# QSFP.net
KiCad netlist of a schematic drawn in Altium Designer
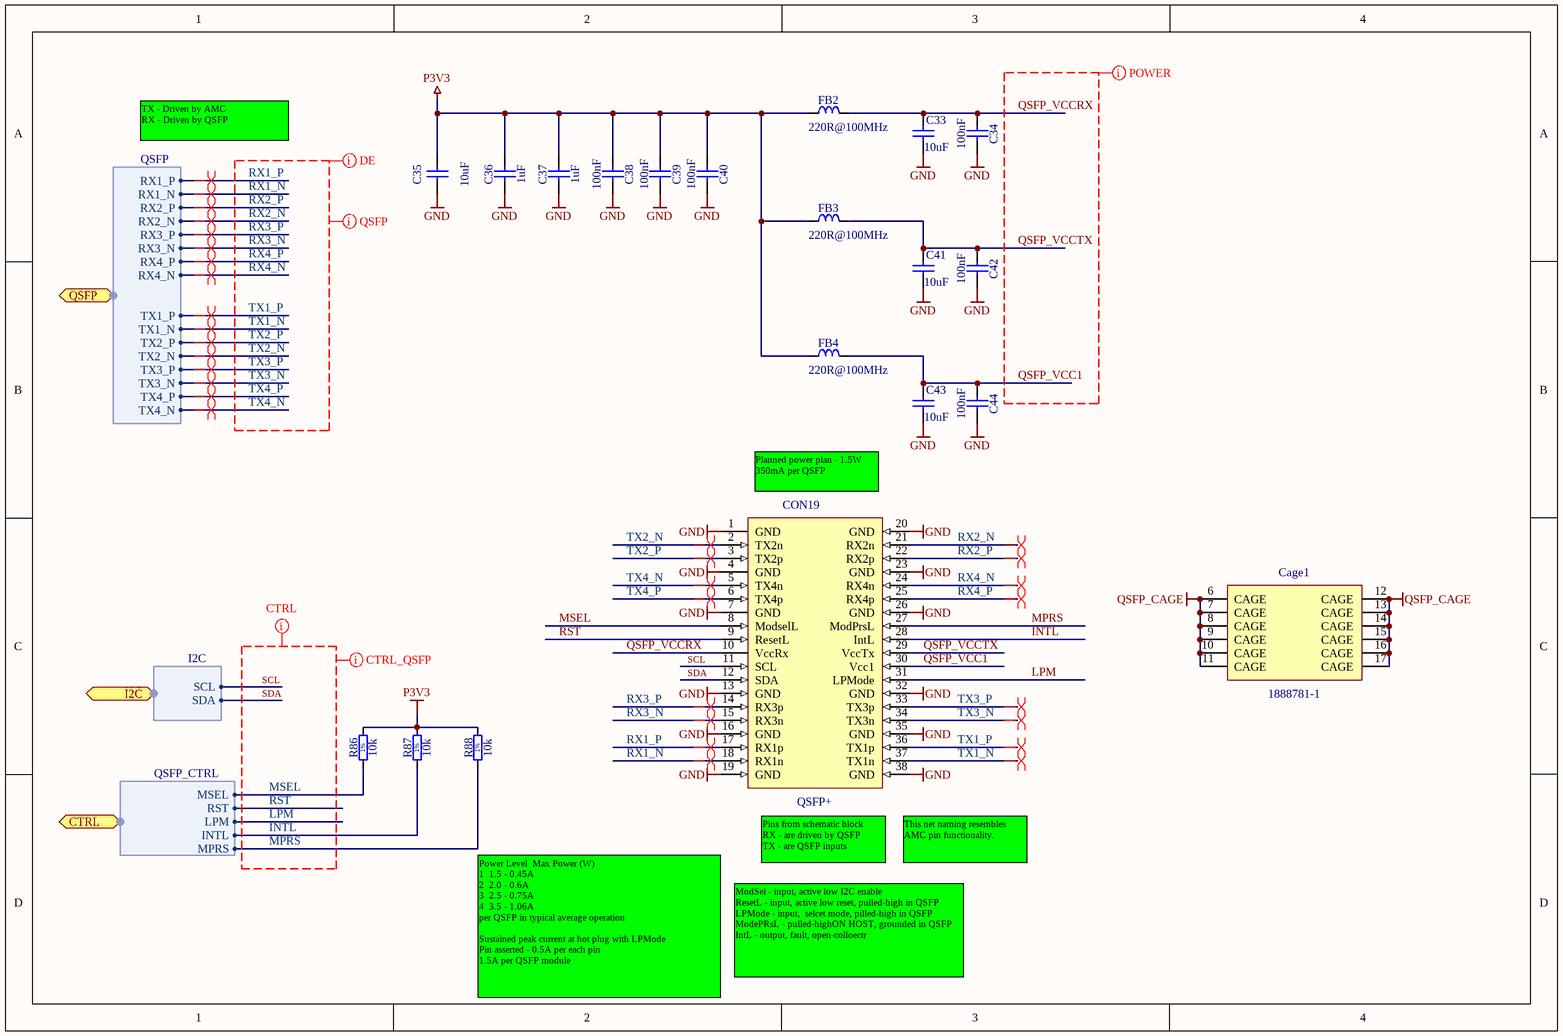
[diagram p0: QSFP.SchDoc]

(export (version "E")
  (design (tool "Eeschema 10.0.6"))
  (components
    (comp (ref "C33")
      (value "10uF")
      (footprint "CAPC2012X135N")
      (description "Non-polarised capacitor")
      (fields
        (field (name "PART NUMBER") "CC0805_10UF_10V_10%_X7R")
        (field (name "VOLTAGE") "10V")
        (field (name "AUTHOR") "CERN DEM JLC")
      )
      (libsource (lib "Capacitors") (part "Capacitor - non polarized"))
    )
    (comp (ref "C34")
      (value "100nF")
      (footprint "CAPC0603X33N")
      (description "Non-polarised capacitor")
      (fields
        (field (name "PART NUMBER") "CC0201_100NF_6.3V_10%_X5R")
        (field (name "VOLTAGE") "6.3V")
        (field (name "AUTHOR") "CERN DEM JLC")
      )
      (libsource (lib "Capacitors") (part "Capacitor - non polarized"))
    )
    (comp (ref "C35")
      (value "10uF")
      (footprint "CAPC2012X135N")
      (description "Non-polarised capacitor")
      (fields
        (field (name "PART NUMBER") "CC0805_10UF_10V_10%_X7R")
        (field (name "VOLTAGE") "10V")
        (field (name "AUTHOR") "CERN DEM JLC")
      )
      (libsource (lib "Capacitors") (part "Capacitor - non polarized"))
    )
    (comp (ref "C36")
      (value "1uF")
      (footprint "CAPC1608X87N")
      (description "Non-polarised capacitor")
      (fields
        (field (name "PART NUMBER") "CC0603_1UF_25V_10%_X7R")
        (field (name "VOLTAGE") "25V")
        (field (name "AUTHOR") "CERN DEM JLC")
      )
      (libsource (lib "Capacitors") (part "Capacitor - non polarized"))
    )
    (comp (ref "C37")
      (value "1uF")
      (footprint "CAPC1608X87N")
      (description "Non-polarised capacitor")
      (fields
        (field (name "PART NUMBER") "CC0603_1UF_25V_10%_X7R")
        (field (name "VOLTAGE") "25V")
        (field (name "AUTHOR") "CERN DEM JLC")
      )
      (libsource (lib "Capacitors") (part "Capacitor - non polarized"))
    )
    (comp (ref "C38")
      (value "100nF")
      (footprint "CAPC0603X33N")
      (description "Non-polarised capacitor")
      (fields
        (field (name "PART NUMBER") "CC0201_100NF_6.3V_10%_X5R")
        (field (name "VOLTAGE") "6.3V")
        (field (name "AUTHOR") "CERN DEM JLC")
      )
      (libsource (lib "Capacitors") (part "Capacitor - non polarized"))
    )
    (comp (ref "C39")
      (value "100nF")
      (footprint "CAPC0603X33N")
      (description "Non-polarised capacitor")
      (fields
        (field (name "PART NUMBER") "CC0201_100NF_6.3V_10%_X5R")
        (field (name "VOLTAGE") "6.3V")
        (field (name "AUTHOR") "CERN DEM JLC")
      )
      (libsource (lib "Capacitors") (part "Capacitor - non polarized"))
    )
    (comp (ref "C40")
      (value "100nF")
      (footprint "CAPC0603X33N")
      (description "Non-polarised capacitor")
      (fields
        (field (name "PART NUMBER") "CC0201_100NF_6.3V_10%_X5R")
        (field (name "VOLTAGE") "6.3V")
        (field (name "AUTHOR") "CERN DEM JLC")
      )
      (libsource (lib "Capacitors") (part "Capacitor - non polarized"))
    )
    (comp (ref "C41")
      (value "10uF")
      (footprint "CAPC2012X135N")
      (description "Non-polarised capacitor")
      (fields
        (field (name "PART NUMBER") "CC0805_10UF_10V_10%_X7R")
        (field (name "VOLTAGE") "10V")
        (field (name "AUTHOR") "CERN DEM JLC")
      )
      (libsource (lib "Capacitors") (part "Capacitor - non polarized"))
    )
    (comp (ref "C42")
      (value "100nF")
      (footprint "CAPC0603X33N")
      (description "Non-polarised capacitor")
      (fields
        (field (name "PART NUMBER") "CC0201_100NF_6.3V_10%_X5R")
        (field (name "VOLTAGE") "6.3V")
        (field (name "AUTHOR") "CERN DEM JLC")
      )
      (libsource (lib "Capacitors") (part "Capacitor - non polarized"))
    )
    (comp (ref "C43")
      (value "10uF")
      (footprint "CAPC2012X135N")
      (description "Non-polarised capacitor")
      (fields
        (field (name "PART NUMBER") "CC0805_10UF_10V_10%_X7R")
        (field (name "VOLTAGE") "10V")
        (field (name "AUTHOR") "CERN DEM JLC")
      )
      (libsource (lib "Capacitors") (part "Capacitor - non polarized"))
    )
    (comp (ref "C44")
      (value "100nF")
      (footprint "CAPC0603X33N")
      (description "Non-polarised capacitor")
      (fields
        (field (name "PART NUMBER") "CC0201_100NF_6.3V_10%_X5R")
        (field (name "VOLTAGE") "6.3V")
        (field (name "AUTHOR") "CERN DEM JLC")
      )
      (libsource (lib "Capacitors") (part "Capacitor - non polarized"))
    )
    (comp (ref "Cage1")
      (value "1888781-1")
      (footprint "TYCO_1888617-1")
      (description "QSFP+ 1x3 Cage (23Pins)")
      (fields
        (field (name "PART NUMBER") "TYCO_2007456-1")
        (field (name "MANUFACTURER") "TYCO ELECTRONICS")
        (field (name "AUTHOR") "CERN DEM JLC")
      )
      (libsource (lib "LIBRARY_SCH") (part "CON_QSFP+_cage"))
    )
    (comp (ref "CON19")
      (value "QSFP+")
      (footprint "TYCO_1761987-9")
      (description "38Position QSFP Connector  (Quad Small Form-factor Pluggable)")
      (fields
        (field (name "PART NUMBER") "TYCO_1761987-9")
        (field (name "MANUFACTURER") "TYCO ELECTRONICS")
        (field (name "AUTHOR") "CERN DEM JLC")
      )
      (libsource (lib "Connectors") (part "QSFP+x1"))
    )
    (comp (ref "FB2")
      (value "220R@100MHz")
      (footprint "INDC2012X105N")
      (description "Inductor")
      (fields
        (field (name "PART NUMBER") "IND0805_MURATA_BLM21PG221SN1D")
        (field (name "POWER") "2A")
        (field (name "AUTHOR") "CERN DEM JLC")
      )
      (libsource (lib "Inductors & Transformers") (part "Inductor"))
    )
    (comp (ref "FB3")
      (value "220R@100MHz")
      (footprint "INDC2012X105N")
      (description "Inductor")
      (fields
        (field (name "PART NUMBER") "IND0805_MURATA_BLM21PG221SN1D")
        (field (name "POWER") "2A")
        (field (name "AUTHOR") "CERN DEM JLC")
      )
      (libsource (lib "Inductors & Transformers") (part "Inductor"))
    )
    (comp (ref "FB4")
      (value "220R@100MHz")
      (footprint "INDC2012X105N")
      (description "Inductor")
      (fields
        (field (name "PART NUMBER") "IND0805_MURATA_BLM21PG221SN1D")
        (field (name "POWER") "2A")
        (field (name "AUTHOR") "CERN DEM JLC")
      )
      (libsource (lib "Inductors & Transformers") (part "Inductor"))
    )
    (comp (ref "R86")
      (value "10k")
      (footprint "RESC1005X40N")
      (description "Resistor - 1%")
      (fields
        (field (name "PART NUMBER") "R0402_10K_1%_0.0625W_100PPM")
        (field (name "POWER") "0.0625W")
        (field (name "AUTHOR") "CERN DEM JLC")
      )
      (libsource (lib "Resistors") (part "Resistor - 1%"))
    )
    (comp (ref "R87")
      (value "10k")
      (footprint "RESC1005X40N")
      (description "Resistor - 1%")
      (fields
        (field (name "PART NUMBER") "R0402_10K_1%_0.0625W_100PPM")
        (field (name "POWER") "0.0625W")
        (field (name "AUTHOR") "CERN DEM JLC")
      )
      (libsource (lib "Resistors") (part "Resistor - 1%"))
    )
    (comp (ref "R88")
      (value "10k")
      (footprint "RESC1005X40N")
      (description "Resistor - 1%")
      (fields
        (field (name "PART NUMBER") "R0402_10K_1%_0.0625W_100PPM")
        (field (name "POWER") "0.0625W")
        (field (name "AUTHOR") "CERN DEM JLC")
      )
      (libsource (lib "Resistors") (part "Resistor - 1%"))
    )
  )
  (nets
    (net (code "4") (name "/INTL") (class "Default")
      (node (ref "CON19") (pin "28") (pinfunction "IntL_28") (pintype "input"))
      (node (ref "R87") (pin "1") (pinfunction "1_1") (pintype "passive"))
    )
    (net (code "5") (name "/LPM") (class "Default")
      (node (ref "CON19") (pin "31") (pinfunction "LPMode_31") (pintype "input"))
    )
    (net (code "6") (name "/MPRS") (class "Default")
      (node (ref "CON19") (pin "27") (pinfunction "ModPrsL_27") (pintype "input"))
      (node (ref "R88") (pin "1") (pinfunction "1_1") (pintype "passive"))
    )
    (net (code "7") (name "/MSEL") (class "Default")
      (node (ref "CON19") (pin "8") (pinfunction "ModselL_8") (pintype "input"))
      (node (ref "R86") (pin "1") (pinfunction "1_1") (pintype "passive"))
    )
    (net (code "8") (name "/QSFP_VCC1") (class "Default")
      (node (ref "C43") (pin "1") (pinfunction "1_1") (pintype "passive"))
      (node (ref "C44") (pin "1") (pinfunction "1_1") (pintype "passive"))
      (node (ref "CON19") (pin "30") (pinfunction "Vcc1_30") (pintype "input"))
      (node (ref "FB4") (pin "2") (pinfunction "2_2") (pintype "passive"))
    )
    (net (code "9") (name "/QSFP_VCCRX") (class "Default")
      (node (ref "C33") (pin "1") (pinfunction "1_1") (pintype "passive"))
      (node (ref "C34") (pin "1") (pinfunction "1_1") (pintype "passive"))
      (node (ref "CON19") (pin "10") (pinfunction "VccRx_10") (pintype "power_in"))
      (node (ref "FB2") (pin "2") (pinfunction "2_2") (pintype "passive"))
    )
    (net (code "10") (name "/QSFP_VCCTX") (class "Default")
      (node (ref "C41") (pin "1") (pinfunction "1_1") (pintype "passive"))
      (node (ref "C42") (pin "1") (pinfunction "1_1") (pintype "passive"))
      (node (ref "CON19") (pin "29") (pinfunction "VccTx_29") (pintype "input"))
      (node (ref "FB3") (pin "2") (pinfunction "2_2") (pintype "passive"))
    )
    (net (code "11") (name "/RST") (class "Default")
      (node (ref "CON19") (pin "9") (pinfunction "ResetL_9") (pintype "input"))
    )
    (net (code "12") (name "/RX1_N") (class "Default")
      (node (ref "CON19") (pin "18") (pinfunction "RX1n_18") (pintype "input"))
    )
    (net (code "13") (name "/RX1_P") (class "Default")
      (node (ref "CON19") (pin "17") (pinfunction "RX1p_17") (pintype "input"))
    )
    (net (code "14") (name "/RX2_N") (class "Default")
      (node (ref "CON19") (pin "21") (pinfunction "RX2n_21") (pintype "input"))
    )
    (net (code "15") (name "/RX2_P") (class "Default")
      (node (ref "CON19") (pin "22") (pinfunction "RX2p_22") (pintype "input"))
    )
    (net (code "16") (name "/RX3_N") (class "Default")
      (node (ref "CON19") (pin "15") (pinfunction "RX3n_15") (pintype "input"))
    )
    (net (code "17") (name "/RX3_P") (class "Default")
      (node (ref "CON19") (pin "14") (pinfunction "RX3p_14") (pintype "input"))
    )
    (net (code "18") (name "/RX4_N") (class "Default")
      (node (ref "CON19") (pin "24") (pinfunction "RX4n_24") (pintype "input"))
    )
    (net (code "19") (name "/RX4_P") (class "Default")
      (node (ref "CON19") (pin "25") (pinfunction "RX4p_25") (pintype "input"))
    )
    (net (code "20") (name "/SCL") (class "Default")
      (node (ref "CON19") (pin "11") (pinfunction "SCL_11") (pintype "input"))
    )
    (net (code "21") (name "/SDA") (class "Default")
      (node (ref "CON19") (pin "12") (pinfunction "SDA_12") (pintype "input"))
    )
    (net (code "22") (name "/TX1_N") (class "Default")
      (node (ref "CON19") (pin "37") (pinfunction "TX1n_37") (pintype "input"))
    )
    (net (code "23") (name "/TX1_P") (class "Default")
      (node (ref "CON19") (pin "36") (pinfunction "TX1p_36") (pintype "input"))
    )
    (net (code "24") (name "/TX2_N") (class "Default")
      (node (ref "CON19") (pin "2") (pinfunction "TX2n_2") (pintype "input"))
    )
    (net (code "25") (name "/TX2_P") (class "Default")
      (node (ref "CON19") (pin "3") (pinfunction "TX2p_3") (pintype "input"))
    )
    (net (code "26") (name "/TX3_N") (class "Default")
      (node (ref "CON19") (pin "34") (pinfunction "TX3n_34") (pintype "input"))
    )
    (net (code "27") (name "/TX3_P") (class "Default")
      (node (ref "CON19") (pin "33") (pinfunction "TX3p_33") (pintype "input"))
    )
    (net (code "28") (name "/TX4_N") (class "Default")
      (node (ref "CON19") (pin "5") (pinfunction "TX4n_5") (pintype "input"))
    )
    (net (code "29") (name "/TX4_P") (class "Default")
      (node (ref "CON19") (pin "6") (pinfunction "TX4p_6") (pintype "input"))
    )
    (net (code "33") (name "GND") (class "Default")
      (node (ref "C33") (pin "2") (pinfunction "2_2") (pintype "passive"))
      (node (ref "C34") (pin "2") (pinfunction "2_2") (pintype "passive"))
      (node (ref "C35") (pin "2") (pinfunction "2_2") (pintype "passive"))
      (node (ref "C36") (pin "1") (pinfunction "1_1") (pintype "passive"))
      (node (ref "C37") (pin "1") (pinfunction "1_1") (pintype "passive"))
      (node (ref "C38") (pin "2") (pinfunction "2_2") (pintype "passive"))
      (node (ref "C39") (pin "2") (pinfunction "2_2") (pintype "passive"))
      (node (ref "C40") (pin "2") (pinfunction "2_2") (pintype "passive"))
      (node (ref "C41") (pin "2") (pinfunction "2_2") (pintype "passive"))
      (node (ref "C42") (pin "2") (pinfunction "2_2") (pintype "passive"))
      (node (ref "C43") (pin "2") (pinfunction "2_2") (pintype "passive"))
      (node (ref "C44") (pin "2") (pinfunction "2_2") (pintype "passive"))
      (node (ref "CON19") (pin "1") (pinfunction "GND_1") (pintype "power_in"))
      (node (ref "CON19") (pin "13") (pinfunction "GND_13") (pintype "input"))
      (node (ref "CON19") (pin "16") (pinfunction "GND_16") (pintype "input"))
      (node (ref "CON19") (pin "19") (pinfunction "GND_19") (pintype "input"))
      (node (ref "CON19") (pin "20") (pinfunction "GND_20") (pintype "input"))
      (node (ref "CON19") (pin "23") (pinfunction "GND_23") (pintype "input"))
      (node (ref "CON19") (pin "26") (pinfunction "GND_26") (pintype "input"))
      (node (ref "CON19") (pin "32") (pinfunction "GND_32") (pintype "input"))
      (node (ref "CON19") (pin "35") (pinfunction "GND_35") (pintype "input"))
      (node (ref "CON19") (pin "38") (pinfunction "GND_38") (pintype "input"))
      (node (ref "CON19") (pin "4") (pinfunction "GND_4") (pintype "power_in"))
      (node (ref "CON19") (pin "7") (pinfunction "GND_7") (pintype "power_in"))
    )
    (net (code "34") (name "P3V3") (class "Default")
      (node (ref "C35") (pin "1") (pinfunction "1_1") (pintype "passive"))
      (node (ref "C36") (pin "2") (pinfunction "2_2") (pintype "passive"))
      (node (ref "C37") (pin "2") (pinfunction "2_2") (pintype "passive"))
      (node (ref "C38") (pin "1") (pinfunction "1_1") (pintype "passive"))
      (node (ref "C39") (pin "1") (pinfunction "1_1") (pintype "passive"))
      (node (ref "C40") (pin "1") (pinfunction "1_1") (pintype "passive"))
      (node (ref "FB2") (pin "1") (pinfunction "1_1") (pintype "passive"))
      (node (ref "FB3") (pin "1") (pinfunction "1_1") (pintype "passive"))
      (node (ref "FB4") (pin "1") (pinfunction "1_1") (pintype "passive"))
      (node (ref "R86") (pin "2") (pinfunction "2_2") (pintype "passive"))
      (node (ref "R87") (pin "2") (pinfunction "2_2") (pintype "passive"))
      (node (ref "R88") (pin "2") (pinfunction "2_2") (pintype "passive"))
    )
    (net (code "35") (name "QSFP_CAGE") (class "Default")
      (node (ref "Cage1") (pin "10") (pinfunction "CAGE_10") (pintype "power_in"))
      (node (ref "Cage1") (pin "11") (pinfunction "CAGE_11") (pintype "power_in"))
      (node (ref "Cage1") (pin "12") (pinfunction "CAGE_12") (pintype "power_in"))
      (node (ref "Cage1") (pin "13") (pinfunction "CAGE_13") (pintype "power_in"))
      (node (ref "Cage1") (pin "14") (pinfunction "CAGE_14") (pintype "power_in"))
      (node (ref "Cage1") (pin "15") (pinfunction "CAGE_15") (pintype "power_in"))
      (node (ref "Cage1") (pin "16") (pinfunction "CAGE_16") (pintype "power_in"))
      (node (ref "Cage1") (pin "17") (pinfunction "CAGE_17") (pintype "power_in"))
      (node (ref "Cage1") (pin "6") (pinfunction "CAGE_6") (pintype "power_in"))
      (node (ref "Cage1") (pin "7") (pinfunction "CAGE_7") (pintype "power_in"))
      (node (ref "Cage1") (pin "8") (pinfunction "CAGE_8") (pintype "power_in"))
      (node (ref "Cage1") (pin "9") (pinfunction "CAGE_9") (pintype "power_in"))
    )
  )
)
